# smart_hub_v2_1.net
KiCad netlist of a schematic drawn in EAGLE
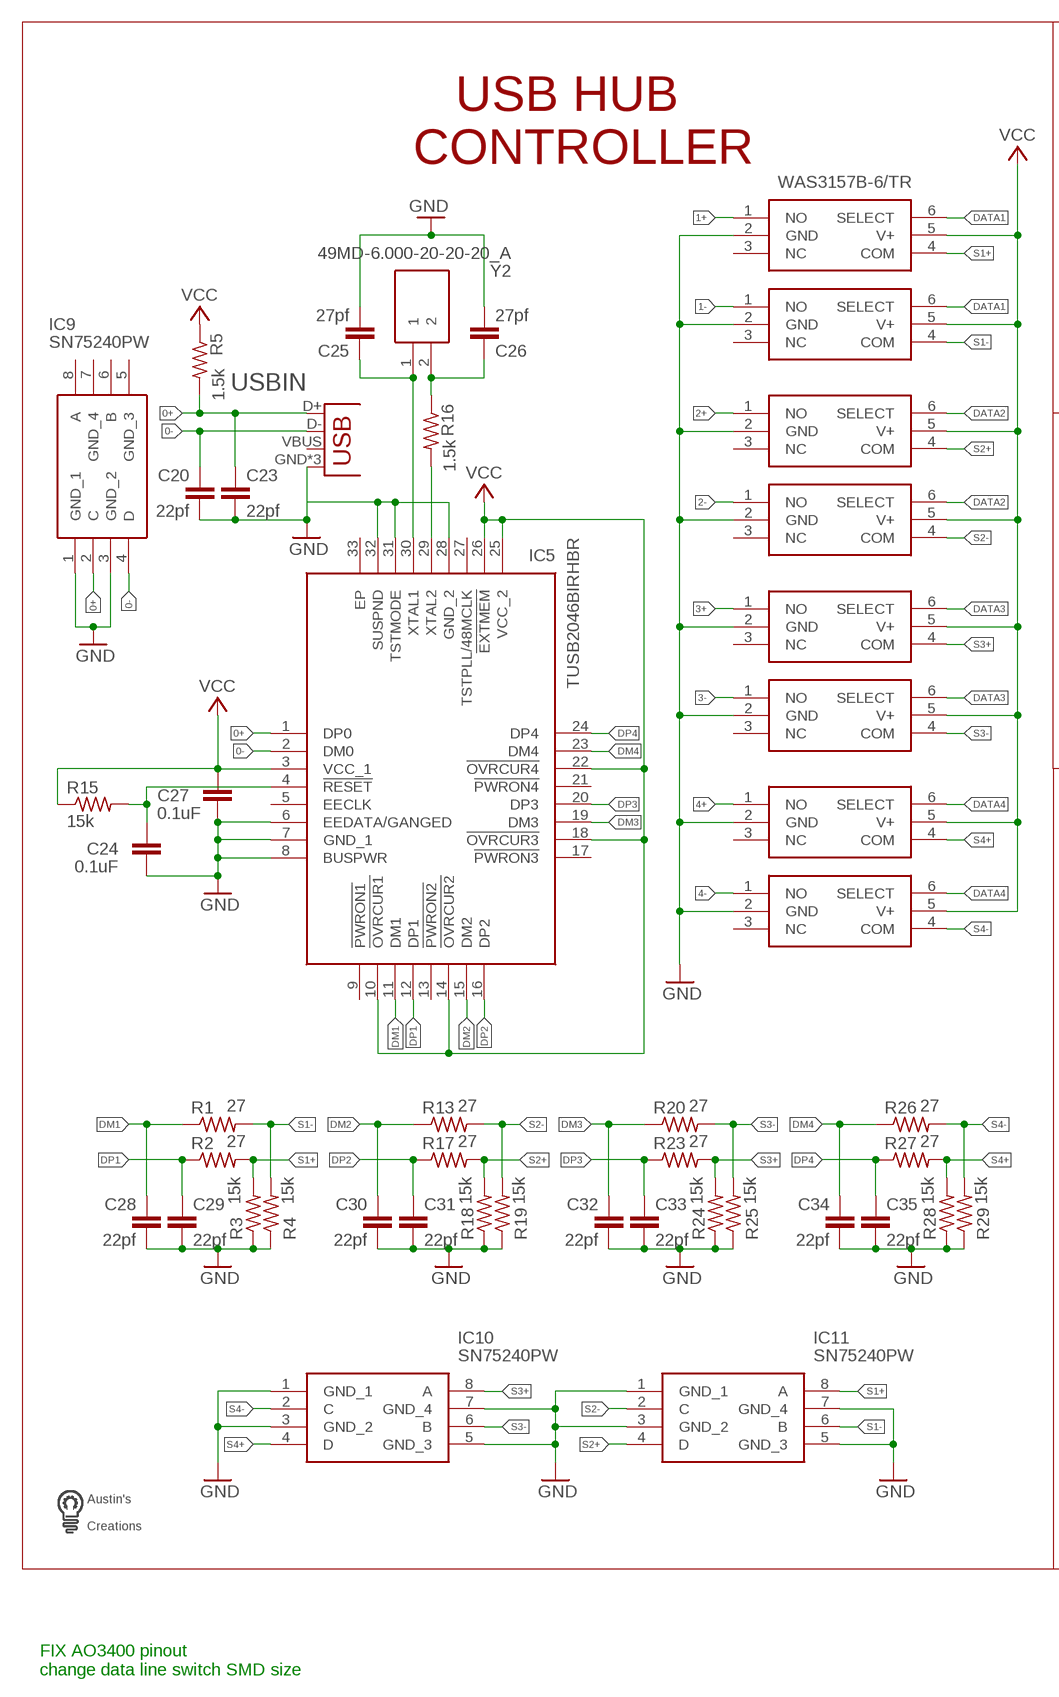
[diagram p0: schematic, sheet 1, part 1 of 2]
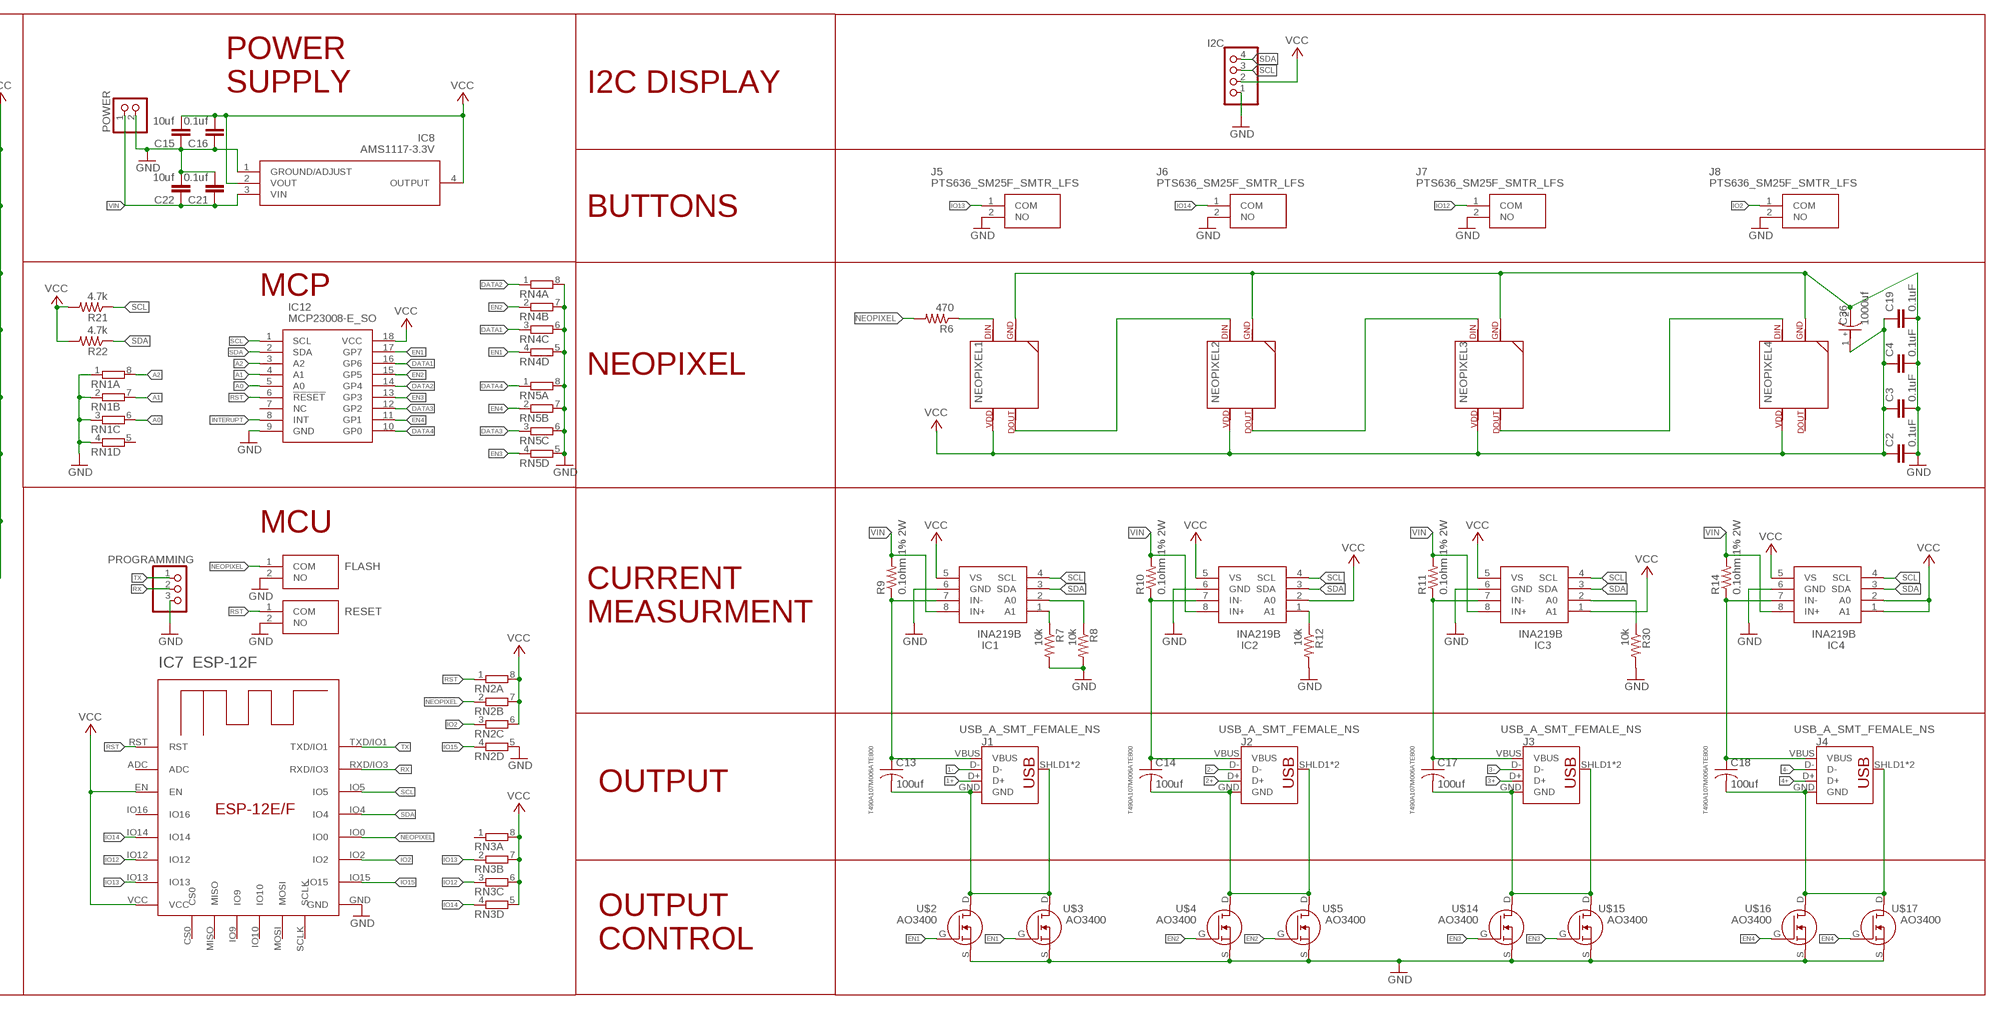
[diagram p1: schematic, sheet 1, part 2 of 2]

(export (version "E")
  (design (tool "Eeschema 10.0.6"))
  (components
    (comp (ref "C2")
      (value "0.1uF")
      (footprint "eagle-import:C0603")
      (libsource (lib "eagle-import") (part "C-EUC0603"))
    )
    (comp (ref "C3")
      (value "0.1uF")
      (footprint "eagle-import:C0603")
      (libsource (lib "eagle-import") (part "C-EUC0603"))
    )
    (comp (ref "C4")
      (value "0.1uF")
      (footprint "eagle-import:C0603")
      (libsource (lib "eagle-import") (part "C-EUC0603"))
    )
    (comp (ref "C13")
      (value "100uf")
      (footprint "eagle-import:C1206")
      (libsource (lib "eagle-import") (part "C-USC1206"))
    )
    (comp (ref "C14")
      (value "100uf")
      (footprint "eagle-import:C1206")
      (libsource (lib "eagle-import") (part "C-USC1206"))
    )
    (comp (ref "C15")
      (value "10uf")
      (footprint "eagle-import:C0603")
      (libsource (lib "eagle-import") (part "C-EUC0603"))
    )
    (comp (ref "C16")
      (value "0.1uf")
      (footprint "eagle-import:C0603")
      (libsource (lib "eagle-import") (part "C-EUC0603"))
    )
    (comp (ref "C17")
      (value "100uf")
      (footprint "eagle-import:C1206")
      (libsource (lib "eagle-import") (part "C-USC1206"))
    )
    (comp (ref "C18")
      (value "100uf")
      (footprint "eagle-import:C1206")
      (libsource (lib "eagle-import") (part "C-USC1206"))
    )
    (comp (ref "C19")
      (value "0.1uF")
      (footprint "eagle-import:C0603")
      (libsource (lib "eagle-import") (part "C-EUC0603"))
    )
    (comp (ref "C20")
      (value "22pf")
      (footprint "eagle-import:C0603")
      (libsource (lib "eagle-import") (part "C-EUC0603"))
    )
    (comp (ref "C21")
      (value "0.1uf")
      (footprint "eagle-import:C0603")
      (libsource (lib "eagle-import") (part "C-EUC0603"))
    )
    (comp (ref "C22")
      (value "10uf")
      (footprint "eagle-import:C0603")
      (libsource (lib "eagle-import") (part "C-EUC0603"))
    )
    (comp (ref "C23")
      (value "22pf")
      (footprint "eagle-import:C0603")
      (libsource (lib "eagle-import") (part "C-EUC0603"))
    )
    (comp (ref "C24")
      (value "0.1uF")
      (footprint "eagle-import:C0603")
      (libsource (lib "eagle-import") (part "C-EUC0603"))
    )
    (comp (ref "C25")
      (value "27pf")
      (footprint "eagle-import:C0603")
      (libsource (lib "eagle-import") (part "C-EUC0603"))
    )
    (comp (ref "C26")
      (value "27pf")
      (footprint "eagle-import:C0603")
      (libsource (lib "eagle-import") (part "C-EUC0603"))
    )
    (comp (ref "C27")
      (value "0.1uF")
      (footprint "eagle-import:C0603")
      (libsource (lib "eagle-import") (part "C-EUC0603"))
    )
    (comp (ref "C28")
      (value "22pf")
      (footprint "eagle-import:C0603")
      (libsource (lib "eagle-import") (part "C-EUC0603"))
    )
    (comp (ref "C29")
      (value "22pf")
      (footprint "eagle-import:C0603")
      (libsource (lib "eagle-import") (part "C-EUC0603"))
    )
    (comp (ref "C30")
      (value "22pf")
      (footprint "eagle-import:C0603")
      (libsource (lib "eagle-import") (part "C-EUC0603"))
    )
    (comp (ref "C31")
      (value "22pf")
      (footprint "eagle-import:C0603")
      (libsource (lib "eagle-import") (part "C-EUC0603"))
    )
    (comp (ref "C32")
      (value "22pf")
      (footprint "eagle-import:C0603")
      (libsource (lib "eagle-import") (part "C-EUC0603"))
    )
    (comp (ref "C33")
      (value "22pf")
      (footprint "eagle-import:C0603")
      (libsource (lib "eagle-import") (part "C-EUC0603"))
    )
    (comp (ref "C34")
      (value "22pf")
      (footprint "eagle-import:C0603")
      (libsource (lib "eagle-import") (part "C-EUC0603"))
    )
    (comp (ref "C35")
      (value "22pf")
      (footprint "eagle-import:C0603")
      (libsource (lib "eagle-import") (part "C-EUC0603"))
    )
    (comp (ref "C36")
      (value "1000uf")
      (footprint "eagle-import:CAPAE1030X1050N")
      (fields
        (field (name "MANUFACTURER_PART_NUMBER") "EEE-0JA102P")
        (field (name "MOUSER_PART_NUMBER") "667-EEE-0JA102P")
      )
      (libsource (lib "eagle-import") (part "EEE-0JA102P"))
    )
    (comp (ref "FLASH")
      (value "PTS636_SM25F_SMTR_LFS")
      (footprint "eagle-import:PTS636SM25FSMTRLFS")
      (fields
        (field (name "ARROW_PART_NUMBER") "PTS636 SM25F SMTR LFS")
        (field (name "MOUSER_PART_NUMBER") "611-PTS636SM25FSMTRL")
      )
      (libsource (lib "eagle-import") (part "PTS636_SM25F_SMTR_LFS"))
    )
    (comp (ref "I2C")
      (value "PINHD-1X4")
      (footprint "eagle-import:1X04")
      (libsource (lib "eagle-import") (part "PINHD-1X4"))
    )
    (comp (ref "IC1")
      (value "INA219B")
      (footprint "eagle-import:SOIC127P600X175-8N")
      (fields
        (field (name "ARROW_PART_NUMBER") "INA219AIDR")
        (field (name "MOUSER_PART_NUMBER") "595-INA219AIDR")
      )
      (libsource (lib "eagle-import") (part "INA219AIDR"))
    )
    (comp (ref "IC2")
      (value "INA219B")
      (footprint "eagle-import:SOIC127P600X175-8N")
      (fields
        (field (name "ARROW_PART_NUMBER") "INA219AIDR")
        (field (name "MOUSER_PART_NUMBER") "595-INA219AIDR")
      )
      (libsource (lib "eagle-import") (part "INA219AIDR"))
    )
    (comp (ref "IC3")
      (value "INA219B")
      (footprint "eagle-import:SOIC127P600X175-8N")
      (fields
        (field (name "ARROW_PART_NUMBER") "INA219AIDR")
        (field (name "MOUSER_PART_NUMBER") "595-INA219AIDR")
      )
      (libsource (lib "eagle-import") (part "INA219AIDR"))
    )
    (comp (ref "IC4")
      (value "INA219B")
      (footprint "eagle-import:SOIC127P600X175-8N")
      (fields
        (field (name "ARROW_PART_NUMBER") "INA219AIDR")
        (field (name "MOUSER_PART_NUMBER") "595-INA219AIDR")
      )
      (libsource (lib "eagle-import") (part "INA219AIDR"))
    )
    (comp (ref "IC5")
      (value "TUSB2046BIRHBR")
      (footprint "eagle-import:QFN50P500X500X100-33N")
      (fields (field (name "MOUSER_PART_NUMBER") "595-TUSB2046BIRHBR"))
      (libsource (lib "eagle-import") (part "TUSB2046BIRHBR"))
    )
    (comp (ref "IC7")
      (value "ESP-12F")
      (footprint "eagle-import:ESP-12E")
      (libsource (lib "eagle-import") (part "ESP-12E/F"))
    )
    (comp (ref "IC8")
      (value "AMS1117-3.3V")
      (footprint "eagle-import:SOT229P700X180-4N")
      (fields (field (name "MANUFACTURER_PART_NUMBER") "ams1117-3.3v"))
      (libsource (lib "eagle-import") (part "AMS1117-3.3V"))
    )
    (comp (ref "IC9")
      (value "SN75240PW")
      (footprint "eagle-import:SOP65P640X120-8N")
      (fields (field (name "MOUSER_PART_NUMBER") "595-SN75240PW"))
      (libsource (lib "eagle-import") (part "SN75240PW"))
    )
    (comp (ref "IC10")
      (value "SN75240PW")
      (footprint "eagle-import:SOP65P640X120-8N")
      (fields (field (name "MOUSER_PART_NUMBER") "595-SN75240PW"))
      (libsource (lib "eagle-import") (part "SN75240PW"))
    )
    (comp (ref "IC11")
      (value "SN75240PW")
      (footprint "eagle-import:SOP65P640X120-8N")
      (fields (field (name "MOUSER_PART_NUMBER") "595-SN75240PW"))
      (libsource (lib "eagle-import") (part "SN75240PW"))
    )
    (comp (ref "IC12")
      (value "MCP23008-E_SO")
      (footprint "eagle-import:SOIC127P1030X265-18N")
      (fields
        (field (name "ARROW_PART_NUMBER") "MCP23008-E/SO")
        (field (name "MOUSER_PART_NUMBER") "579-MCP23008-E/SO")
      )
      (libsource (lib "eagle-import") (part "MCP23008-E_SO"))
    )
    (comp (ref "J1")
      (value "USB_A_SMT_FEMALE_NS")
      (footprint "eagle-import:USB-A-S-NOSILK-FEMALE")
      (libsource (lib "eagle-import") (part "USB_A_SMT_FEMALE_NS"))
    )
    (comp (ref "J2")
      (value "USB_A_SMT_FEMALE_NS")
      (footprint "eagle-import:USB-A-S-NOSILK-FEMALE")
      (libsource (lib "eagle-import") (part "USB_A_SMT_FEMALE_NS"))
    )
    (comp (ref "J3")
      (value "USB_A_SMT_FEMALE_NS")
      (footprint "eagle-import:USB-A-S-NOSILK-FEMALE")
      (libsource (lib "eagle-import") (part "USB_A_SMT_FEMALE_NS"))
    )
    (comp (ref "J4")
      (value "USB_A_SMT_FEMALE_NS")
      (footprint "eagle-import:USB-A-S-NOSILK-FEMALE")
      (libsource (lib "eagle-import") (part "USB_A_SMT_FEMALE_NS"))
    )
    (comp (ref "J5")
      (value "PTS636_SM25F_SMTR_LFS")
      (footprint "eagle-import:PTS636SM25FSMTRLFS")
      (fields
        (field (name "ARROW_PART_NUMBER") "PTS636 SM25F SMTR LFS")
        (field (name "MOUSER_PART_NUMBER") "611-PTS636SM25FSMTRL")
      )
      (libsource (lib "eagle-import") (part "PTS636_SM25F_SMTR_LFS"))
    )
    (comp (ref "J6")
      (value "PTS636_SM25F_SMTR_LFS")
      (footprint "eagle-import:PTS636SM25FSMTRLFS")
      (fields
        (field (name "ARROW_PART_NUMBER") "PTS636 SM25F SMTR LFS")
        (field (name "MOUSER_PART_NUMBER") "611-PTS636SM25FSMTRL")
      )
      (libsource (lib "eagle-import") (part "PTS636_SM25F_SMTR_LFS"))
    )
    (comp (ref "J7")
      (value "PTS636_SM25F_SMTR_LFS")
      (footprint "eagle-import:PTS636SM25FSMTRLFS")
      (fields
        (field (name "ARROW_PART_NUMBER") "PTS636 SM25F SMTR LFS")
        (field (name "MOUSER_PART_NUMBER") "611-PTS636SM25FSMTRL")
      )
      (libsource (lib "eagle-import") (part "PTS636_SM25F_SMTR_LFS"))
    )
    (comp (ref "J8")
      (value "PTS636_SM25F_SMTR_LFS")
      (footprint "eagle-import:PTS636SM25FSMTRLFS")
      (fields
        (field (name "ARROW_PART_NUMBER") "PTS636 SM25F SMTR LFS")
        (field (name "MOUSER_PART_NUMBER") "611-PTS636SM25FSMTRL")
      )
      (libsource (lib "eagle-import") (part "PTS636_SM25F_SMTR_LFS"))
    )
    (comp (ref "NEOPIXEL1")
      (value "SK6812NEOPIXEL5050")
      (footprint "eagle-import:SK6812")
      (libsource (lib "eagle-import") (part "SK68125050NEOPIXEL"))
    )
    (comp (ref "NEOPIXEL2")
      (value "SK6812NEOPIXEL5050")
      (footprint "eagle-import:SK6812")
      (libsource (lib "eagle-import") (part "SK68125050NEOPIXEL"))
    )
    (comp (ref "NEOPIXEL3")
      (value "SK6812NEOPIXEL5050")
      (footprint "eagle-import:SK6812")
      (libsource (lib "eagle-import") (part "SK68125050NEOPIXEL"))
    )
    (comp (ref "NEOPIXEL4")
      (value "SK6812NEOPIXEL5050")
      (footprint "eagle-import:SK6812")
      (libsource (lib "eagle-import") (part "SK68125050NEOPIXEL"))
    )
    (comp (ref "POWER")
      (value "PINHD-1X2")
      (footprint "eagle-import:1X02")
      (libsource (lib "eagle-import") (part "PINHD-1X2"))
    )
    (comp (ref "PROGRAMMING")
      (value "PINHD-1X3")
      (footprint "eagle-import:1X03")
      (libsource (lib "eagle-import") (part "PINHD-1X3"))
    )
    (comp (ref "R1")
      (value "27")
      (footprint "eagle-import:R0603")
      (libsource (lib "eagle-import") (part "R-US_R0603"))
    )
    (comp (ref "R2")
      (value "27")
      (footprint "eagle-import:R0603")
      (libsource (lib "eagle-import") (part "R-US_R0603"))
    )
    (comp (ref "R3")
      (value "15k")
      (footprint "eagle-import:R0603")
      (libsource (lib "eagle-import") (part "R-US_R0603"))
    )
    (comp (ref "R4")
      (value "15k")
      (footprint "eagle-import:R0603")
      (libsource (lib "eagle-import") (part "R-US_R0603"))
    )
    (comp (ref "R5")
      (value "1.5k")
      (footprint "eagle-import:R0603")
      (libsource (lib "eagle-import") (part "R-US_R0603"))
    )
    (comp (ref "R6")
      (value "470")
      (footprint "eagle-import:R0603")
      (libsource (lib "eagle-import") (part "R-US_R0603"))
    )
    (comp (ref "R7")
      (value "10k")
      (footprint "eagle-import:R0603")
      (libsource (lib "eagle-import") (part "R-US_R0603"))
    )
    (comp (ref "R8")
      (value "10k")
      (footprint "eagle-import:R0603")
      (libsource (lib "eagle-import") (part "R-US_R0603"))
    )
    (comp (ref "R9")
      (value "0.1ohm 1% 2W")
      (footprint "eagle-import:R2512W")
      (libsource (lib "eagle-import") (part "R-US_R2512W"))
    )
    (comp (ref "R10")
      (value "0.1ohm 1% 2W")
      (footprint "eagle-import:R2512W")
      (libsource (lib "eagle-import") (part "R-US_R2512W"))
    )
    (comp (ref "R11")
      (value "0.1ohm 1% 2W")
      (footprint "eagle-import:R2512W")
      (libsource (lib "eagle-import") (part "R-US_R2512W"))
    )
    (comp (ref "R12")
      (value "10k")
      (footprint "eagle-import:R0603")
      (libsource (lib "eagle-import") (part "R-US_R0603"))
    )
    (comp (ref "R13")
      (value "27")
      (footprint "eagle-import:R0603")
      (libsource (lib "eagle-import") (part "R-US_R0603"))
    )
    (comp (ref "R14")
      (value "0.1ohm 1% 2W")
      (footprint "eagle-import:R2512W")
      (libsource (lib "eagle-import") (part "R-US_R2512W"))
    )
    (comp (ref "R15")
      (value "15k")
      (footprint "eagle-import:R0603")
      (libsource (lib "eagle-import") (part "R-US_R0603"))
    )
    (comp (ref "R16")
      (value "1.5k")
      (footprint "eagle-import:R0603")
      (libsource (lib "eagle-import") (part "R-US_R0603"))
    )
    (comp (ref "R17")
      (value "27")
      (footprint "eagle-import:R0603")
      (libsource (lib "eagle-import") (part "R-US_R0603"))
    )
    (comp (ref "R18")
      (value "15k")
      (footprint "eagle-import:R0603")
      (libsource (lib "eagle-import") (part "R-US_R0603"))
    )
    (comp (ref "R19")
      (value "15k")
      (footprint "eagle-import:R0603")
      (libsource (lib "eagle-import") (part "R-US_R0603"))
    )
    (comp (ref "R20")
      (value "27")
      (footprint "eagle-import:R0603")
      (libsource (lib "eagle-import") (part "R-US_R0603"))
    )
    (comp (ref "R21")
      (value "4.7k")
      (footprint "eagle-import:R0603")
      (libsource (lib "eagle-import") (part "R-US_R0603"))
    )
    (comp (ref "R22")
      (value "4.7k")
      (footprint "eagle-import:R0603")
      (libsource (lib "eagle-import") (part "R-US_R0603"))
    )
    (comp (ref "R23")
      (value "27")
      (footprint "eagle-import:R0603")
      (libsource (lib "eagle-import") (part "R-US_R0603"))
    )
    (comp (ref "R24")
      (value "15k")
      (footprint "eagle-import:R0603")
      (libsource (lib "eagle-import") (part "R-US_R0603"))
    )
    (comp (ref "R25")
      (value "15k")
      (footprint "eagle-import:R0603")
      (libsource (lib "eagle-import") (part "R-US_R0603"))
    )
    (comp (ref "R26")
      (value "27")
      (footprint "eagle-import:R0603")
      (libsource (lib "eagle-import") (part "R-US_R0603"))
    )
    (comp (ref "R27")
      (value "27")
      (footprint "eagle-import:R0603")
      (libsource (lib "eagle-import") (part "R-US_R0603"))
    )
    (comp (ref "R28")
      (value "15k")
      (footprint "eagle-import:R0603")
      (libsource (lib "eagle-import") (part "R-US_R0603"))
    )
    (comp (ref "R29")
      (value "15k")
      (footprint "eagle-import:R0603")
      (libsource (lib "eagle-import") (part "R-US_R0603"))
    )
    (comp (ref "R30")
      (value "10k")
      (footprint "eagle-import:R0603")
      (libsource (lib "eagle-import") (part "R-US_R0603"))
    )
    (comp (ref "RESET")
      (value "PTS636_SM25F_SMTR_LFS")
      (footprint "eagle-import:PTS636SM25FSMTRLFS")
      (fields
        (field (name "ARROW_PART_NUMBER") "PTS636 SM25F SMTR LFS")
        (field (name "MOUSER_PART_NUMBER") "611-PTS636SM25FSMTRL")
      )
      (libsource (lib "eagle-import") (part "PTS636_SM25F_SMTR_LFS"))
    )
    (comp (ref "RN1")
      (value "4R-N0603-ARC")
      (footprint "eagle-import:0603-ARC")
      (libsource (lib "eagle-import") (part "4R-N0603-ARC"))
    )
    (comp (ref "RN2")
      (value "4R-N0603-ARC")
      (footprint "eagle-import:0603-ARC")
      (libsource (lib "eagle-import") (part "4R-N0603-ARC"))
    )
    (comp (ref "RN3")
      (value "4R-N0603-ARC")
      (footprint "eagle-import:0603-ARC")
      (libsource (lib "eagle-import") (part "4R-N0603-ARC"))
    )
    (comp (ref "RN4")
      (value "4R-N0603-ARC")
      (footprint "eagle-import:0603-ARC")
      (libsource (lib "eagle-import") (part "4R-N0603-ARC"))
    )
    (comp (ref "RN5")
      (value "4R-N0603-ARC")
      (footprint "eagle-import:0603-ARC")
      (libsource (lib "eagle-import") (part "4R-N0603-ARC"))
    )
    (comp (ref "U$1")
      (value "LOGOMASSIVE")
      (footprint "eagle-import:LOGOMASSIVE")
      (libsource (lib "eagle-import") (part "LOGOMASSIVE"))
    )
    (comp (ref "U$2")
      (value "AO3400")
      (footprint "eagle-import:AO3400")
      (libsource (lib "eagle-import") (part "AO3400"))
    )
    (comp (ref "U$3")
      (value "AO3400")
      (footprint "eagle-import:AO3400")
      (libsource (lib "eagle-import") (part "AO3400"))
    )
    (comp (ref "U$4")
      (value "AO3400")
      (footprint "eagle-import:AO3400")
      (libsource (lib "eagle-import") (part "AO3400"))
    )
    (comp (ref "U$5")
      (value "AO3400")
      (footprint "eagle-import:AO3400")
      (libsource (lib "eagle-import") (part "AO3400"))
    )
    (comp (ref "U$6")
      (value "WAS3157B-6/TR")
      (footprint "eagle-import:WAS3157B-6_TR")
      (libsource (lib "eagle-import") (part "WAS3157B-6/TR"))
    )
    (comp (ref "U$7")
      (value "WAS3157B-6/TR")
      (footprint "eagle-import:WAS3157B-6_TR")
      (libsource (lib "eagle-import") (part "WAS3157B-6/TR"))
    )
    (comp (ref "U$8")
      (value "WAS3157B-6/TR")
      (footprint "eagle-import:WAS3157B-6_TR")
      (libsource (lib "eagle-import") (part "WAS3157B-6/TR"))
    )
    (comp (ref "U$9")
      (value "WAS3157B-6/TR")
      (footprint "eagle-import:WAS3157B-6_TR")
      (libsource (lib "eagle-import") (part "WAS3157B-6/TR"))
    )
    (comp (ref "U$10")
      (value "WAS3157B-6/TR")
      (footprint "eagle-import:WAS3157B-6_TR")
      (libsource (lib "eagle-import") (part "WAS3157B-6/TR"))
    )
    (comp (ref "U$11")
      (value "WAS3157B-6/TR")
      (footprint "eagle-import:WAS3157B-6_TR")
      (libsource (lib "eagle-import") (part "WAS3157B-6/TR"))
    )
    (comp (ref "U$12")
      (value "WAS3157B-6/TR")
      (footprint "eagle-import:WAS3157B-6_TR")
      (libsource (lib "eagle-import") (part "WAS3157B-6/TR"))
    )
    (comp (ref "U$13")
      (value "WAS3157B-6/TR")
      (footprint "eagle-import:WAS3157B-6_TR")
      (libsource (lib "eagle-import") (part "WAS3157B-6/TR"))
    )
    (comp (ref "U$14")
      (value "AO3400")
      (footprint "eagle-import:AO3400")
      (libsource (lib "eagle-import") (part "AO3400"))
    )
    (comp (ref "U$15")
      (value "AO3400")
      (footprint "eagle-import:AO3400")
      (libsource (lib "eagle-import") (part "AO3400"))
    )
    (comp (ref "U$16")
      (value "AO3400")
      (footprint "eagle-import:AO3400")
      (libsource (lib "eagle-import") (part "AO3400"))
    )
    (comp (ref "U$17")
      (value "AO3400")
      (footprint "eagle-import:AO3400")
      (libsource (lib "eagle-import") (part "AO3400"))
    )
    (comp (ref "USBIN")
      (value "USB-MICROB")
      (footprint "eagle-import:USB-MICROB")
      (libsource (lib "eagle-import") (part "USB-MICROB"))
    )
    (comp (ref "Y2")
      (value "49MD-6.000-20-20-20_A")
      (footprint "eagle-import:49MD6000202020A")
      (fields (field (name "MANUFACTURER_PART_NUMBER") "49MD-6.000-20-20-20/A"))
      (libsource (lib "eagle-import") (part "49MD-6.000-20-20-20_A"))
    )
  )
  (nets
    (net (code "1") (name "0+") (class "Default")
      (node (ref "C23") (pin "1") (pinfunction "1_1") (pintype "passive"))
      (node (ref "IC5") (pin "1") (pinfunction "DP0_1") (pintype "bidirectional"))
      (node (ref "IC9") (pin "2") (pinfunction "C_2") (pintype "bidirectional"))
      (node (ref "R5") (pin "2") (pinfunction "2_2") (pintype "passive"))
      (node (ref "USBIN") (pin "D+") (pinfunction "D+_D+") (pintype "bidirectional"))
    )
    (net (code "2") (name "0-") (class "Default")
      (node (ref "C20") (pin "1") (pinfunction "1_1") (pintype "passive"))
      (node (ref "IC5") (pin "2") (pinfunction "DM0_2") (pintype "bidirectional"))
      (node (ref "IC9") (pin "4") (pinfunction "D_4") (pintype "bidirectional"))
      (node (ref "USBIN") (pin "D-") (pinfunction "D-_D-") (pintype "bidirectional"))
    )
    (net (code "3") (name "1+") (class "Default")
      (node (ref "J1") (pin "D+") (pinfunction "D+_D+") (pintype "bidirectional"))
      (node (ref "U$6") (pin "1") (pinfunction "NO_1") (pintype "bidirectional"))
    )
    (net (code "4") (name "1-") (class "Default")
      (node (ref "J1") (pin "D-") (pinfunction "D-_D-") (pintype "bidirectional"))
      (node (ref "U$7") (pin "1") (pinfunction "NO_1") (pintype "bidirectional"))
    )
    (net (code "5") (name "2+") (class "Default")
      (node (ref "J2") (pin "D+") (pinfunction "D+_D+") (pintype "bidirectional"))
      (node (ref "U$8") (pin "1") (pinfunction "NO_1") (pintype "bidirectional"))
    )
    (net (code "6") (name "2-") (class "Default")
      (node (ref "J2") (pin "D-") (pinfunction "D-_D-") (pintype "bidirectional"))
      (node (ref "U$9") (pin "1") (pinfunction "NO_1") (pintype "bidirectional"))
    )
    (net (code "7") (name "3+") (class "Default")
      (node (ref "J3") (pin "D+") (pinfunction "D+_D+") (pintype "bidirectional"))
      (node (ref "U$10") (pin "1") (pinfunction "NO_1") (pintype "bidirectional"))
    )
    (net (code "8") (name "3-") (class "Default")
      (node (ref "J3") (pin "D-") (pinfunction "D-_D-") (pintype "bidirectional"))
      (node (ref "U$11") (pin "1") (pinfunction "NO_1") (pintype "bidirectional"))
    )
    (net (code "9") (name "4+") (class "Default")
      (node (ref "J4") (pin "D+") (pinfunction "D+_D+") (pintype "bidirectional"))
      (node (ref "U$12") (pin "1") (pinfunction "NO_1") (pintype "bidirectional"))
    )
    (net (code "10") (name "4-") (class "Default")
      (node (ref "J4") (pin "D-") (pinfunction "D-_D-") (pintype "bidirectional"))
      (node (ref "U$13") (pin "1") (pinfunction "NO_1") (pintype "bidirectional"))
    )
    (net (code "11") (name "A0") (class "Default")
      (node (ref "IC12") (pin "5") (pinfunction "A0_5") (pintype "bidirectional"))
      (node (ref "RN1") (pin "6") (pinfunction "2_6") (pintype "passive"))
    )
    (net (code "12") (name "A1") (class "Default")
      (node (ref "IC12") (pin "4") (pinfunction "A1_4") (pintype "bidirectional"))
      (node (ref "RN1") (pin "7") (pinfunction "2_7") (pintype "passive"))
    )
    (net (code "13") (name "A2") (class "Default")
      (node (ref "IC12") (pin "3") (pinfunction "A2_3") (pintype "bidirectional"))
      (node (ref "RN1") (pin "8") (pinfunction "2_8") (pintype "passive"))
    )
    (net (code "14") (name "DATA1") (class "Default")
      (node (ref "IC12") (pin "16") (pinfunction "GP6_16") (pintype "bidirectional"))
      (node (ref "RN4") (pin "3") (pinfunction "1_3") (pintype "passive"))
      (node (ref "U$6") (pin "6") (pinfunction "SELECT_6") (pintype "bidirectional"))
      (node (ref "U$7") (pin "6") (pinfunction "SELECT_6") (pintype "bidirectional"))
    )
    (net (code "15") (name "DATA2") (class "Default")
      (node (ref "IC12") (pin "14") (pinfunction "GP4_14") (pintype "bidirectional"))
      (node (ref "RN4") (pin "1") (pinfunction "1_1") (pintype "passive"))
      (node (ref "U$8") (pin "6") (pinfunction "SELECT_6") (pintype "bidirectional"))
      (node (ref "U$9") (pin "6") (pinfunction "SELECT_6") (pintype "bidirectional"))
    )
    (net (code "16") (name "DATA3") (class "Default")
      (node (ref "IC12") (pin "12") (pinfunction "GP2_12") (pintype "bidirectional"))
      (node (ref "RN5") (pin "3") (pinfunction "1_3") (pintype "passive"))
      (node (ref "U$10") (pin "6") (pinfunction "SELECT_6") (pintype "bidirectional"))
      (node (ref "U$11") (pin "6") (pinfunction "SELECT_6") (pintype "bidirectional"))
    )
    (net (code "17") (name "DATA4") (class "Default")
      (node (ref "IC12") (pin "10") (pinfunction "GP0_10") (pintype "bidirectional"))
      (node (ref "RN5") (pin "1") (pinfunction "1_1") (pintype "passive"))
      (node (ref "U$12") (pin "6") (pinfunction "SELECT_6") (pintype "bidirectional"))
      (node (ref "U$13") (pin "6") (pinfunction "SELECT_6") (pintype "bidirectional"))
    )
    (net (code "18") (name "DM1") (class "Default")
      (node (ref "C28") (pin "1") (pinfunction "1_1") (pintype "passive"))
      (node (ref "IC5") (pin "11") (pinfunction "DM1_11") (pintype "bidirectional"))
      (node (ref "R1") (pin "1") (pinfunction "1_1") (pintype "passive"))
    )
    (net (code "19") (name "DM2") (class "Default")
      (node (ref "C30") (pin "1") (pinfunction "1_1") (pintype "passive"))
      (node (ref "IC5") (pin "15") (pinfunction "DM2_15") (pintype "bidirectional"))
      (node (ref "R13") (pin "1") (pinfunction "1_1") (pintype "passive"))
    )
    (net (code "20") (name "DM3") (class "Default")
      (node (ref "C32") (pin "1") (pinfunction "1_1") (pintype "passive"))
      (node (ref "IC5") (pin "19") (pinfunction "DM3_19") (pintype "bidirectional"))
      (node (ref "R20") (pin "1") (pinfunction "1_1") (pintype "passive"))
    )
    (net (code "21") (name "DM4") (class "Default")
      (node (ref "C34") (pin "1") (pinfunction "1_1") (pintype "passive"))
      (node (ref "IC5") (pin "23") (pinfunction "DM4_23") (pintype "bidirectional"))
      (node (ref "R26") (pin "1") (pinfunction "1_1") (pintype "passive"))
    )
    (net (code "22") (name "DP1") (class "Default")
      (node (ref "C29") (pin "1") (pinfunction "1_1") (pintype "passive"))
      (node (ref "IC5") (pin "12") (pinfunction "DP1_12") (pintype "bidirectional"))
      (node (ref "R2") (pin "1") (pinfunction "1_1") (pintype "passive"))
    )
    (net (code "23") (name "DP2") (class "Default")
      (node (ref "C31") (pin "1") (pinfunction "1_1") (pintype "passive"))
      (node (ref "IC5") (pin "16") (pinfunction "DP2_16") (pintype "bidirectional"))
      (node (ref "R17") (pin "1") (pinfunction "1_1") (pintype "passive"))
    )
    (net (code "24") (name "DP3") (class "Default")
      (node (ref "C33") (pin "1") (pinfunction "1_1") (pintype "passive"))
      (node (ref "IC5") (pin "20") (pinfunction "DP3_20") (pintype "bidirectional"))
      (node (ref "R23") (pin "1") (pinfunction "1_1") (pintype "passive"))
    )
    (net (code "25") (name "DP4") (class "Default")
      (node (ref "C35") (pin "1") (pinfunction "1_1") (pintype "passive"))
      (node (ref "IC5") (pin "24") (pinfunction "DP4_24") (pintype "bidirectional"))
      (node (ref "R27") (pin "1") (pinfunction "1_1") (pintype "passive"))
    )
    (net (code "26") (name "EN1") (class "Default")
      (node (ref "IC12") (pin "17") (pinfunction "GP7_17") (pintype "bidirectional"))
      (node (ref "RN4") (pin "4") (pinfunction "1_4") (pintype "passive"))
      (node (ref "U$2") (pin "G") (pinfunction "G_G") (pintype "bidirectional"))
      (node (ref "U$3") (pin "G") (pinfunction "G_G") (pintype "bidirectional"))
    )
    (net (code "27") (name "EN2") (class "Default")
      (node (ref "IC12") (pin "15") (pinfunction "GP5_15") (pintype "bidirectional"))
      (node (ref "RN4") (pin "2") (pinfunction "1_2") (pintype "passive"))
      (node (ref "U$4") (pin "G") (pinfunction "G_G") (pintype "bidirectional"))
      (node (ref "U$5") (pin "G") (pinfunction "G_G") (pintype "bidirectional"))
    )
    (net (code "28") (name "EN3") (class "Default")
      (node (ref "IC12") (pin "13") (pinfunction "GP3_13") (pintype "bidirectional"))
      (node (ref "RN5") (pin "4") (pinfunction "1_4") (pintype "passive"))
      (node (ref "U$14") (pin "G") (pinfunction "G_G") (pintype "bidirectional"))
      (node (ref "U$15") (pin "G") (pinfunction "G_G") (pintype "bidirectional"))
    )
    (net (code "29") (name "EN4") (class "Default")
      (node (ref "IC12") (pin "11") (pinfunction "GP1_11") (pintype "bidirectional"))
      (node (ref "RN5") (pin "2") (pinfunction "1_2") (pintype "passive"))
      (node (ref "U$16") (pin "G") (pinfunction "G_G") (pintype "bidirectional"))
      (node (ref "U$17") (pin "G") (pinfunction "G_G") (pintype "bidirectional"))
    )
    (net (code "30") (name "GND") (class "Default")
      (node (ref "C15") (pin "1") (pinfunction "1_1") (pintype "passive"))
      (node (ref "C16") (pin "1") (pinfunction "1_1") (pintype "passive"))
      (node (ref "C19") (pin "2") (pinfunction "2_2") (pintype "passive"))
      (node (ref "C2") (pin "2") (pinfunction "2_2") (pintype "passive"))
      (node (ref "C20") (pin "2") (pinfunction "2_2") (pintype "passive"))
      (node (ref "C21") (pin "2") (pinfunction "2_2") (pintype "passive"))
      (node (ref "C22") (pin "2") (pinfunction "2_2") (pintype "passive"))
      (node (ref "C23") (pin "2") (pinfunction "2_2") (pintype "passive"))
      (node (ref "C24") (pin "2") (pinfunction "2_2") (pintype "passive"))
      (node (ref "C25") (pin "2") (pinfunction "2_2") (pintype "passive"))
      (node (ref "C26") (pin "2") (pinfunction "2_2") (pintype "passive"))
      (node (ref "C27") (pin "2") (pinfunction "2_2") (pintype "passive"))
      (node (ref "C28") (pin "2") (pinfunction "2_2") (pintype "passive"))
      (node (ref "C29") (pin "2") (pinfunction "2_2") (pintype "passive"))
      (node (ref "C3") (pin "2") (pinfunction "2_2") (pintype "passive"))
      (node (ref "C30") (pin "2") (pinfunction "2_2") (pintype "passive"))
      (node (ref "C31") (pin "2") (pinfunction "2_2") (pintype "passive"))
      (node (ref "C32") (pin "2") (pinfunction "2_2") (pintype "passive"))
      (node (ref "C33") (pin "2") (pinfunction "2_2") (pintype "passive"))
      (node (ref "C34") (pin "2") (pinfunction "2_2") (pintype "passive"))
      (node (ref "C35") (pin "2") (pinfunction "2_2") (pintype "passive"))
      (node (ref "C36") (pin "2") (pinfunction "-_2") (pintype "bidirectional"))
      (node (ref "C4") (pin "2") (pinfunction "2_2") (pintype "passive"))
      (node (ref "FLASH") (pin "2") (pinfunction "NO_2") (pintype "bidirectional"))
      (node (ref "I2C") (pin "1") (pinfunction "1_1") (pintype "passive"))
      (node (ref "IC1") (pin "6") (pinfunction "GND_6") (pintype "bidirectional"))
      (node (ref "IC10") (pin "1") (pinfunction "GND_1_1") (pintype "bidirectional"))
      (node (ref "IC10") (pin "3") (pinfunction "GND_2_3") (pintype "bidirectional"))
      (node (ref "IC10") (pin "5") (pinfunction "GND_3_5") (pintype "bidirectional"))
      (node (ref "IC10") (pin "7") (pinfunction "GND_4_7") (pintype "bidirectional"))
      (node (ref "IC11") (pin "1") (pinfunction "GND_1_1") (pintype "bidirectional"))
      (node (ref "IC11") (pin "3") (pinfunction "GND_2_3") (pintype "bidirectional"))
      (node (ref "IC11") (pin "5") (pinfunction "GND_3_5") (pintype "bidirectional"))
      (node (ref "IC11") (pin "7") (pinfunction "GND_4_7") (pintype "bidirectional"))
      (node (ref "IC12") (pin "9") (pinfunction "GND_9") (pintype "bidirectional"))
      (node (ref "IC2") (pin "6") (pinfunction "GND_6") (pintype "bidirectional"))
      (node (ref "IC3") (pin "6") (pinfunction "GND_6") (pintype "bidirectional"))
      (node (ref "IC4") (pin "6") (pinfunction "GND_6") (pintype "bidirectional"))
      (node (ref "IC5") (pin "28") (pinfunction "GND_2_28") (pintype "bidirectional"))
      (node (ref "IC5") (pin "31") (pinfunction "TSTMODE_31") (pintype "bidirectional"))
      (node (ref "IC5") (pin "32") (pinfunction "SUSPND_32") (pintype "bidirectional"))
      (node (ref "IC5") (pin "6") (pinfunction "EEDATA/GANGED_6") (pintype "bidirectional"))
      (node (ref "IC5") (pin "7") (pinfunction "GND_1_7") (pintype "bidirectional"))
      (node (ref "IC5") (pin "8") (pinfunction "BUSPWR_8") (pintype "bidirectional"))
      (node (ref "IC7") (pin "GND") (pinfunction "GND_GND") (pintype "power_in"))
      (node (ref "IC8") (pin "1") (pinfunction "GROUND/ADJUST_1") (pintype "bidirectional"))
      (node (ref "IC9") (pin "1") (pinfunction "GND_1_1") (pintype "bidirectional"))
      (node (ref "IC9") (pin "3") (pinfunction "GND_2_3") (pintype "bidirectional"))
      (node (ref "J5") (pin "2") (pinfunction "NO_2") (pintype "bidirectional"))
      (node (ref "J6") (pin "2") (pinfunction "NO_2") (pintype "bidirectional"))
      (node (ref "J7") (pin "2") (pinfunction "NO_2") (pintype "bidirectional"))
      (node (ref "J8") (pin "2") (pinfunction "NO_2") (pintype "bidirectional"))
      (node (ref "NEOPIXEL1") (pin "3") (pinfunction "GND_3") (pintype "bidirectional"))
      (node (ref "NEOPIXEL2") (pin "3") (pinfunction "GND_3") (pintype "bidirectional"))
      (node (ref "NEOPIXEL3") (pin "3") (pinfunction "GND_3") (pintype "bidirectional"))
      (node (ref "NEOPIXEL4") (pin "3") (pinfunction "GND_3") (pintype "bidirectional"))
      (node (ref "POWER") (pin "2") (pinfunction "2_2") (pintype "passive"))
      (node (ref "PROGRAMMING") (pin "3") (pinfunction "3_3") (pintype "passive"))
      (node (ref "R12") (pin "2") (pinfunction "2_2") (pintype "passive"))
      (node (ref "R18") (pin "1") (pinfunction "1_1") (pintype "passive"))
      (node (ref "R19") (pin "1") (pinfunction "1_1") (pintype "passive"))
      (node (ref "R24") (pin "1") (pinfunction "1_1") (pintype "passive"))
      (node (ref "R25") (pin "1") (pinfunction "1_1") (pintype "passive"))
      (node (ref "R28") (pin "1") (pinfunction "1_1") (pintype "passive"))
      (node (ref "R29") (pin "1") (pinfunction "1_1") (pintype "passive"))
      (node (ref "R3") (pin "1") (pinfunction "1_1") (pintype "passive"))
      (node (ref "R30") (pin "2") (pinfunction "2_2") (pintype "passive"))
      (node (ref "R4") (pin "1") (pinfunction "1_1") (pintype "passive"))
      (node (ref "R7") (pin "2") (pinfunction "2_2") (pintype "passive"))
      (node (ref "R8") (pin "2") (pinfunction "2_2") (pintype "passive"))
      (node (ref "RESET") (pin "2") (pinfunction "NO_2") (pintype "bidirectional"))
      (node (ref "RN1") (pin "1") (pinfunction "1_1") (pintype "passive"))
      (node (ref "RN1") (pin "2") (pinfunction "1_2") (pintype "passive"))
      (node (ref "RN1") (pin "3") (pinfunction "1_3") (pintype "passive"))
      (node (ref "RN1") (pin "4") (pinfunction "1_4") (pintype "passive"))
      (node (ref "RN2") (pin "5") (pinfunction "2_5") (pintype "passive"))
      (node (ref "RN4") (pin "5") (pinfunction "2_5") (pintype "passive"))
      (node (ref "RN4") (pin "6") (pinfunction "2_6") (pintype "passive"))
      (node (ref "RN4") (pin "7") (pinfunction "2_7") (pintype "passive"))
      (node (ref "RN4") (pin "8") (pinfunction "2_8") (pintype "passive"))
      (node (ref "RN5") (pin "5") (pinfunction "2_5") (pintype "passive"))
      (node (ref "RN5") (pin "6") (pinfunction "2_6") (pintype "passive"))
      (node (ref "RN5") (pin "7") (pinfunction "2_7") (pintype "passive"))
      (node (ref "RN5") (pin "8") (pinfunction "2_8") (pintype "passive"))
      (node (ref "U$10") (pin "2") (pinfunction "GND_2") (pintype "bidirectional"))
      (node (ref "U$11") (pin "2") (pinfunction "GND_2") (pintype "bidirectional"))
      (node (ref "U$12") (pin "2") (pinfunction "GND_2") (pintype "bidirectional"))
      (node (ref "U$13") (pin "2") (pinfunction "GND_2") (pintype "bidirectional"))
      (node (ref "U$14") (pin "S") (pinfunction "S_S") (pintype "bidirectional"))
      (node (ref "U$15") (pin "S") (pinfunction "S_S") (pintype "bidirectional"))
      (node (ref "U$16") (pin "S") (pinfunction "S_S") (pintype "bidirectional"))
      (node (ref "U$17") (pin "S") (pinfunction "S_S") (pintype "bidirectional"))
      (node (ref "U$2") (pin "S") (pinfunction "S_S") (pintype "bidirectional"))
      (node (ref "U$3") (pin "S") (pinfunction "S_S") (pintype "bidirectional"))
      (node (ref "U$4") (pin "S") (pinfunction "S_S") (pintype "bidirectional"))
      (node (ref "U$5") (pin "S") (pinfunction "S_S") (pintype "bidirectional"))
      (node (ref "U$6") (pin "2") (pinfunction "GND_2") (pintype "bidirectional"))
      (node (ref "U$7") (pin "2") (pinfunction "GND_2") (pintype "bidirectional"))
      (node (ref "U$8") (pin "2") (pinfunction "GND_2") (pintype "bidirectional"))
      (node (ref "U$9") (pin "2") (pinfunction "GND_2") (pintype "bidirectional"))
      (node (ref "USBIN") (pin "GND") (pinfunction "GND_GND") (pintype "bidirectional"))
      (node (ref "USBIN") (pin "MT1") (pinfunction "GND_MT1") (pintype "bidirectional"))
      (node (ref "USBIN") (pin "MT2") (pinfunction "GND_MT2") (pintype "bidirectional"))
    )
    (net (code "31") (name "INTERUPT") (class "Default")
      (node (ref "IC12") (pin "8") (pinfunction "INT_8") (pintype "bidirectional"))
    )
    (net (code "32") (name "IO2") (class "Default")
      (node (ref "IC7") (pin "IO2") (pinfunction "IO2_IO2") (pintype "bidirectional"))
      (node (ref "J8") (pin "1") (pinfunction "COM_1") (pintype "bidirectional"))
      (node (ref "RN2") (pin "3") (pinfunction "1_3") (pintype "passive"))
    )
    (net (code "33") (name "IO12") (class "Default")
      (node (ref "IC7") (pin "IO12") (pinfunction "IO12_IO12") (pintype "bidirectional"))
      (node (ref "J7") (pin "1") (pinfunction "COM_1") (pintype "bidirectional"))
      (node (ref "RN3") (pin "3") (pinfunction "1_3") (pintype "passive"))
    )
    (net (code "34") (name "IO13") (class "Default")
      (node (ref "IC7") (pin "IO13") (pinfunction "IO13_IO13") (pintype "bidirectional"))
      (node (ref "J5") (pin "1") (pinfunction "COM_1") (pintype "bidirectional"))
      (node (ref "RN3") (pin "2") (pinfunction "1_2") (pintype "passive"))
    )
    (net (code "35") (name "IO14") (class "Default")
      (node (ref "IC7") (pin "IO14") (pinfunction "IO14_IO14") (pintype "bidirectional"))
      (node (ref "J6") (pin "1") (pinfunction "COM_1") (pintype "bidirectional"))
      (node (ref "RN3") (pin "4") (pinfunction "1_4") (pintype "passive"))
    )
    (net (code "36") (name "IO15") (class "Default")
      (node (ref "IC7") (pin "IO15") (pinfunction "IO15_IO15") (pintype "bidirectional"))
      (node (ref "RN2") (pin "4") (pinfunction "1_4") (pintype "passive"))
    )
    (net (code "37") (name "NEOPIXEL") (class "Default")
      (node (ref "FLASH") (pin "1") (pinfunction "COM_1") (pintype "bidirectional"))
      (node (ref "IC7") (pin "IO0") (pinfunction "IO0_IO0") (pintype "bidirectional"))
      (node (ref "R6") (pin "2") (pinfunction "2_2") (pintype "passive"))
      (node (ref "RN2") (pin "2") (pinfunction "1_2") (pintype "passive"))
    )
    (net (code "38") (name "Net-(C13-Pad2)") (class "Default")
      (node (ref "C13") (pin "2") (pinfunction "2_2") (pintype "passive"))
      (node (ref "J1") (pin "GND") (pinfunction "GND_GND") (pintype "power_in"))
      (node (ref "J1") (pin "SHLD1") (pinfunction "SHIELD_SHLD1") (pintype "bidirectional"))
      (node (ref "J1") (pin "SHLD2") (pinfunction "SHIELD_SHLD2") (pintype "bidirectional"))
      (node (ref "U$2") (pin "D") (pinfunction "D_D") (pintype "bidirectional"))
      (node (ref "U$3") (pin "D") (pinfunction "D_D") (pintype "bidirectional"))
    )
    (net (code "39") (name "Net-(C14-Pad2)") (class "Default")
      (node (ref "C14") (pin "2") (pinfunction "2_2") (pintype "passive"))
      (node (ref "J2") (pin "GND") (pinfunction "GND_GND") (pintype "power_in"))
      (node (ref "J2") (pin "SHLD1") (pinfunction "SHIELD_SHLD1") (pintype "bidirectional"))
      (node (ref "J2") (pin "SHLD2") (pinfunction "SHIELD_SHLD2") (pintype "bidirectional"))
      (node (ref "U$4") (pin "D") (pinfunction "D_D") (pintype "bidirectional"))
      (node (ref "U$5") (pin "D") (pinfunction "D_D") (pintype "bidirectional"))
    )
    (net (code "40") (name "Net-(C17-Pad2)") (class "Default")
      (node (ref "C17") (pin "2") (pinfunction "2_2") (pintype "passive"))
      (node (ref "J3") (pin "GND") (pinfunction "GND_GND") (pintype "power_in"))
      (node (ref "J3") (pin "SHLD1") (pinfunction "SHIELD_SHLD1") (pintype "bidirectional"))
      (node (ref "J3") (pin "SHLD2") (pinfunction "SHIELD_SHLD2") (pintype "bidirectional"))
      (node (ref "U$14") (pin "D") (pinfunction "D_D") (pintype "bidirectional"))
      (node (ref "U$15") (pin "D") (pinfunction "D_D") (pintype "bidirectional"))
    )
    (net (code "41") (name "Net-(C18-Pad2)") (class "Default")
      (node (ref "C18") (pin "2") (pinfunction "2_2") (pintype "passive"))
      (node (ref "J4") (pin "GND") (pinfunction "GND_GND") (pintype "power_in"))
      (node (ref "J4") (pin "SHLD1") (pinfunction "SHIELD_SHLD1") (pintype "bidirectional"))
      (node (ref "J4") (pin "SHLD2") (pinfunction "SHIELD_SHLD2") (pintype "bidirectional"))
      (node (ref "U$16") (pin "D") (pinfunction "D_D") (pintype "bidirectional"))
      (node (ref "U$17") (pin "D") (pinfunction "D_D") (pintype "bidirectional"))
    )
    (net (code "42") (name "Net-(C26-Pad1)") (class "Default")
      (node (ref "C26") (pin "1") (pinfunction "1_1") (pintype "passive"))
      (node (ref "R16") (pin "1") (pinfunction "1_1") (pintype "passive"))
      (node (ref "Y2") (pin "2") (pinfunction "2_2") (pintype "bidirectional"))
    )
    (net (code "43") (name "Net-(IC1-A0)") (class "Default")
      (node (ref "IC1") (pin "2") (pinfunction "A0_2") (pintype "bidirectional"))
      (node (ref "R8") (pin "1") (pinfunction "1_1") (pintype "passive"))
    )
    (net (code "44") (name "Net-(IC1-A1)") (class "Default")
      (node (ref "IC1") (pin "1") (pinfunction "A1_1") (pintype "bidirectional"))
      (node (ref "R7") (pin "1") (pinfunction "1_1") (pintype "passive"))
    )
    (net (code "45") (name "Net-(IC1-IN-)") (class "Default")
      (node (ref "C13") (pin "1") (pinfunction "1_1") (pintype "passive"))
      (node (ref "IC1") (pin "7") (pinfunction "IN-_7") (pintype "bidirectional"))
      (node (ref "J1") (pin "VBUS") (pinfunction "VBUS_VBUS") (pintype "power_in"))
      (node (ref "R9") (pin "1") (pinfunction "1_1") (pintype "passive"))
    )
    (net (code "46") (name "Net-(IC2-A1)") (class "Default")
      (node (ref "IC2") (pin "1") (pinfunction "A1_1") (pintype "bidirectional"))
      (node (ref "R12") (pin "1") (pinfunction "1_1") (pintype "passive"))
    )
    (net (code "47") (name "Net-(IC2-IN-)") (class "Default")
      (node (ref "C14") (pin "1") (pinfunction "1_1") (pintype "passive"))
      (node (ref "IC2") (pin "7") (pinfunction "IN-_7") (pintype "bidirectional"))
      (node (ref "J2") (pin "VBUS") (pinfunction "VBUS_VBUS") (pintype "power_in"))
      (node (ref "R10") (pin "1") (pinfunction "1_1") (pintype "passive"))
    )
    (net (code "48") (name "Net-(IC3-A0)") (class "Default")
      (node (ref "IC3") (pin "2") (pinfunction "A0_2") (pintype "bidirectional"))
      (node (ref "R30") (pin "1") (pinfunction "1_1") (pintype "passive"))
    )
    (net (code "49") (name "Net-(IC3-IN-)") (class "Default")
      (node (ref "C17") (pin "1") (pinfunction "1_1") (pintype "passive"))
      (node (ref "IC3") (pin "7") (pinfunction "IN-_7") (pintype "bidirectional"))
      (node (ref "J3") (pin "VBUS") (pinfunction "VBUS_VBUS") (pintype "power_in"))
      (node (ref "R11") (pin "1") (pinfunction "1_1") (pintype "passive"))
    )
    (net (code "50") (name "Net-(IC4-IN-)") (class "Default")
      (node (ref "C18") (pin "1") (pinfunction "1_1") (pintype "passive"))
      (node (ref "IC4") (pin "7") (pinfunction "IN-_7") (pintype "bidirectional"))
      (node (ref "J4") (pin "VBUS") (pinfunction "VBUS_VBUS") (pintype "power_in"))
      (node (ref "R14") (pin "1") (pinfunction "1_1") (pintype "passive"))
    )
    (net (code "51") (name "Net-(IC5-XTAL1)") (class "Default")
      (node (ref "C25") (pin "1") (pinfunction "1_1") (pintype "passive"))
      (node (ref "IC5") (pin "30") (pinfunction "XTAL1_30") (pintype "bidirectional"))
      (node (ref "Y2") (pin "1") (pinfunction "1_1") (pintype "bidirectional"))
    )
    (net (code "52") (name "Net-(IC5-XTAL2)") (class "Default")
      (node (ref "IC5") (pin "29") (pinfunction "XTAL2_29") (pintype "bidirectional"))
      (node (ref "R16") (pin "2") (pinfunction "2_2") (pintype "passive"))
    )
    (net (code "53") (name "Net-(IC5-~{RESET})") (class "Default")
      (node (ref "C24") (pin "1") (pinfunction "1_1") (pintype "passive"))
      (node (ref "IC5") (pin "4") (pinfunction "~{RESET}_4") (pintype "bidirectional"))
      (node (ref "R15") (pin "2") (pinfunction "2_2") (pintype "passive"))
    )
    (net (code "54") (name "Net-(NEOPIXEL1-DIN)") (class "Default")
      (node (ref "NEOPIXEL1") (pin "4") (pinfunction "DIN_4") (pintype "bidirectional"))
      (node (ref "R6") (pin "1") (pinfunction "1_1") (pintype "passive"))
    )
    (net (code "55") (name "Net-(NEOPIXEL1-DOUT)") (class "Default")
      (node (ref "NEOPIXEL1") (pin "2") (pinfunction "DOUT_2") (pintype "bidirectional"))
      (node (ref "NEOPIXEL2") (pin "4") (pinfunction "DIN_4") (pintype "bidirectional"))
    )
    (net (code "56") (name "Net-(NEOPIXEL2-DOUT)") (class "Default")
      (node (ref "NEOPIXEL2") (pin "2") (pinfunction "DOUT_2") (pintype "bidirectional"))
      (node (ref "NEOPIXEL3") (pin "4") (pinfunction "DIN_4") (pintype "bidirectional"))
    )
    (net (code "57") (name "Net-(NEOPIXEL3-DOUT)") (class "Default")
      (node (ref "NEOPIXEL3") (pin "2") (pinfunction "DOUT_2") (pintype "bidirectional"))
      (node (ref "NEOPIXEL4") (pin "4") (pinfunction "DIN_4") (pintype "bidirectional"))
    )
    (net (code "58") (name "RST") (class "Default")
      (node (ref "IC12") (pin "6") (pinfunction "~{RESET}_6") (pintype "bidirectional"))
      (node (ref "IC7") (pin "RST") (pinfunction "RST_RST") (pintype "input"))
      (node (ref "RESET") (pin "1") (pinfunction "COM_1") (pintype "bidirectional"))
      (node (ref "RN2") (pin "1") (pinfunction "1_1") (pintype "passive"))
    )
    (net (code "59") (name "RX") (class "Default")
      (node (ref "IC7") (pin "RXD/IO3") (pinfunction "RXD/IO3_RXD/IO3") (pintype "bidirectional"))
      (node (ref "PROGRAMMING") (pin "2") (pinfunction "2_2") (pintype "passive"))
    )
    (net (code "60") (name "S1+") (class "Default")
      (node (ref "IC11") (pin "8") (pinfunction "A_8") (pintype "bidirectional"))
      (node (ref "R2") (pin "2") (pinfunction "2_2") (pintype "passive"))
      (node (ref "R3") (pin "2") (pinfunction "2_2") (pintype "passive"))
      (node (ref "U$6") (pin "4") (pinfunction "COM_4") (pintype "bidirectional"))
    )
    (net (code "61") (name "S1-") (class "Default")
      (node (ref "IC11") (pin "6") (pinfunction "B_6") (pintype "bidirectional"))
      (node (ref "R1") (pin "2") (pinfunction "2_2") (pintype "passive"))
      (node (ref "R4") (pin "2") (pinfunction "2_2") (pintype "passive"))
      (node (ref "U$7") (pin "4") (pinfunction "COM_4") (pintype "bidirectional"))
    )
    (net (code "62") (name "S2+") (class "Default")
      (node (ref "IC11") (pin "4") (pinfunction "D_4") (pintype "bidirectional"))
      (node (ref "R17") (pin "2") (pinfunction "2_2") (pintype "passive"))
      (node (ref "R18") (pin "2") (pinfunction "2_2") (pintype "passive"))
      (node (ref "U$8") (pin "4") (pinfunction "COM_4") (pintype "bidirectional"))
    )
    (net (code "63") (name "S2-") (class "Default")
      (node (ref "IC11") (pin "2") (pinfunction "C_2") (pintype "bidirectional"))
      (node (ref "R13") (pin "2") (pinfunction "2_2") (pintype "passive"))
      (node (ref "R19") (pin "2") (pinfunction "2_2") (pintype "passive"))
      (node (ref "U$9") (pin "4") (pinfunction "COM_4") (pintype "bidirectional"))
    )
    (net (code "64") (name "S3+") (class "Default")
      (node (ref "IC10") (pin "8") (pinfunction "A_8") (pintype "bidirectional"))
      (node (ref "R23") (pin "2") (pinfunction "2_2") (pintype "passive"))
      (node (ref "R24") (pin "2") (pinfunction "2_2") (pintype "passive"))
      (node (ref "U$10") (pin "4") (pinfunction "COM_4") (pintype "bidirectional"))
    )
    (net (code "65") (name "S3-") (class "Default")
      (node (ref "IC10") (pin "6") (pinfunction "B_6") (pintype "bidirectional"))
      (node (ref "R20") (pin "2") (pinfunction "2_2") (pintype "passive"))
      (node (ref "R25") (pin "2") (pinfunction "2_2") (pintype "passive"))
      (node (ref "U$11") (pin "4") (pinfunction "COM_4") (pintype "bidirectional"))
    )
    (net (code "66") (name "S4+") (class "Default")
      (node (ref "IC10") (pin "4") (pinfunction "D_4") (pintype "bidirectional"))
      (node (ref "R27") (pin "2") (pinfunction "2_2") (pintype "passive"))
      (node (ref "R28") (pin "2") (pinfunction "2_2") (pintype "passive"))
      (node (ref "U$12") (pin "4") (pinfunction "COM_4") (pintype "bidirectional"))
    )
    (net (code "67") (name "S4-") (class "Default")
      (node (ref "IC10") (pin "2") (pinfunction "C_2") (pintype "bidirectional"))
      (node (ref "R26") (pin "2") (pinfunction "2_2") (pintype "passive"))
      (node (ref "R29") (pin "2") (pinfunction "2_2") (pintype "passive"))
      (node (ref "U$13") (pin "4") (pinfunction "COM_4") (pintype "bidirectional"))
    )
    (net (code "68") (name "SCL") (class "Default")
      (node (ref "I2C") (pin "3") (pinfunction "3_3") (pintype "passive"))
      (node (ref "IC1") (pin "4") (pinfunction "SCL_4") (pintype "bidirectional"))
      (node (ref "IC12") (pin "1") (pinfunction "SCL_1") (pintype "bidirectional"))
      (node (ref "IC2") (pin "4") (pinfunction "SCL_4") (pintype "bidirectional"))
      (node (ref "IC3") (pin "4") (pinfunction "SCL_4") (pintype "bidirectional"))
      (node (ref "IC4") (pin "4") (pinfunction "SCL_4") (pintype "bidirectional"))
      (node (ref "IC7") (pin "IO5") (pinfunction "IO5_IO5") (pintype "bidirectional"))
      (node (ref "R21") (pin "1") (pinfunction "1_1") (pintype "passive"))
    )
    (net (code "69") (name "SDA") (class "Default")
      (node (ref "I2C") (pin "4") (pinfunction "4_4") (pintype "passive"))
      (node (ref "IC1") (pin "3") (pinfunction "SDA_3") (pintype "bidirectional"))
      (node (ref "IC12") (pin "2") (pinfunction "SDA_2") (pintype "bidirectional"))
      (node (ref "IC2") (pin "3") (pinfunction "SDA_3") (pintype "bidirectional"))
      (node (ref "IC3") (pin "3") (pinfunction "SDA_3") (pintype "bidirectional"))
      (node (ref "IC4") (pin "3") (pinfunction "SDA_3") (pintype "bidirectional"))
      (node (ref "IC7") (pin "IO4") (pinfunction "IO4_IO4") (pintype "bidirectional"))
      (node (ref "R22") (pin "1") (pinfunction "1_1") (pintype "passive"))
    )
    (net (code "70") (name "TX") (class "Default")
      (node (ref "IC7") (pin "TXD/IO1") (pinfunction "TXD/IO1_TXD/IO1") (pintype "bidirectional"))
      (node (ref "PROGRAMMING") (pin "1") (pinfunction "1_1") (pintype "passive"))
    )
    (net (code "71") (name "VCC") (class "Default")
      (node (ref "C15") (pin "2") (pinfunction "2_2") (pintype "passive"))
      (node (ref "C16") (pin "2") (pinfunction "2_2") (pintype "passive"))
      (node (ref "C19") (pin "1") (pinfunction "1_1") (pintype "passive"))
      (node (ref "C2") (pin "1") (pinfunction "1_1") (pintype "passive"))
      (node (ref "C27") (pin "1") (pinfunction "1_1") (pintype "passive"))
      (node (ref "C3") (pin "1") (pinfunction "1_1") (pintype "passive"))
      (node (ref "C36") (pin "1") (pinfunction "+_1") (pintype "bidirectional"))
      (node (ref "C4") (pin "1") (pinfunction "1_1") (pintype "passive"))
      (node (ref "I2C") (pin "2") (pinfunction "2_2") (pintype "passive"))
      (node (ref "IC1") (pin "5") (pinfunction "VS_5") (pintype "bidirectional"))
      (node (ref "IC12") (pin "18") (pinfunction "VCC_18") (pintype "bidirectional"))
      (node (ref "IC2") (pin "2") (pinfunction "A0_2") (pintype "bidirectional"))
      (node (ref "IC2") (pin "5") (pinfunction "VS_5") (pintype "bidirectional"))
      (node (ref "IC3") (pin "1") (pinfunction "A1_1") (pintype "bidirectional"))
      (node (ref "IC3") (pin "5") (pinfunction "VS_5") (pintype "bidirectional"))
      (node (ref "IC4") (pin "1") (pinfunction "A1_1") (pintype "bidirectional"))
      (node (ref "IC4") (pin "2") (pinfunction "A0_2") (pintype "bidirectional"))
      (node (ref "IC4") (pin "5") (pinfunction "VS_5") (pintype "bidirectional"))
      (node (ref "IC5") (pin "10") (pinfunction "~{OVRCUR1}_10") (pintype "bidirectional"))
      (node (ref "IC5") (pin "14") (pinfunction "~{OVRCUR2}_14") (pintype "bidirectional"))
      (node (ref "IC5") (pin "18") (pinfunction "~{OVRCUR3}_18") (pintype "bidirectional"))
      (node (ref "IC5") (pin "22") (pinfunction "~{OVRCUR4}_22") (pintype "bidirectional"))
      (node (ref "IC5") (pin "25") (pinfunction "VCC_2_25") (pintype "bidirectional"))
      (node (ref "IC5") (pin "26") (pinfunction "~{EXTMEM}_26") (pintype "bidirectional"))
      (node (ref "IC5") (pin "3") (pinfunction "VCC_1_3") (pintype "bidirectional"))
      (node (ref "IC7") (pin "EN") (pinfunction "EN_EN") (pintype "bidirectional"))
      (node (ref "IC7") (pin "VCC") (pinfunction "VCC_VCC") (pintype "power_in"))
      (node (ref "IC8") (pin "2") (pinfunction "VOUT_2") (pintype "bidirectional"))
      (node (ref "IC8") (pin "4") (pinfunction "OUTPUT_4") (pintype "bidirectional"))
      (node (ref "NEOPIXEL1") (pin "1") (pinfunction "VDD_1") (pintype "bidirectional"))
      (node (ref "NEOPIXEL2") (pin "1") (pinfunction "VDD_1") (pintype "bidirectional"))
      (node (ref "NEOPIXEL3") (pin "1") (pinfunction "VDD_1") (pintype "bidirectional"))
      (node (ref "NEOPIXEL4") (pin "1") (pinfunction "VDD_1") (pintype "bidirectional"))
      (node (ref "R15") (pin "1") (pinfunction "1_1") (pintype "passive"))
      (node (ref "R21") (pin "2") (pinfunction "2_2") (pintype "passive"))
      (node (ref "R22") (pin "2") (pinfunction "2_2") (pintype "passive"))
      (node (ref "R5") (pin "1") (pinfunction "1_1") (pintype "passive"))
      (node (ref "RN2") (pin "6") (pinfunction "2_6") (pintype "passive"))
      (node (ref "RN2") (pin "7") (pinfunction "2_7") (pintype "passive"))
      (node (ref "RN2") (pin "8") (pinfunction "2_8") (pintype "passive"))
      (node (ref "RN3") (pin "5") (pinfunction "2_5") (pintype "passive"))
      (node (ref "RN3") (pin "6") (pinfunction "2_6") (pintype "passive"))
      (node (ref "RN3") (pin "7") (pinfunction "2_7") (pintype "passive"))
      (node (ref "RN3") (pin "8") (pinfunction "2_8") (pintype "passive"))
      (node (ref "U$10") (pin "5") (pinfunction "V+_5") (pintype "bidirectional"))
      (node (ref "U$11") (pin "5") (pinfunction "V+_5") (pintype "bidirectional"))
      (node (ref "U$12") (pin "5") (pinfunction "V+_5") (pintype "bidirectional"))
      (node (ref "U$13") (pin "5") (pinfunction "V+_5") (pintype "bidirectional"))
      (node (ref "U$6") (pin "5") (pinfunction "V+_5") (pintype "bidirectional"))
      (node (ref "U$7") (pin "5") (pinfunction "V+_5") (pintype "bidirectional"))
      (node (ref "U$8") (pin "5") (pinfunction "V+_5") (pintype "bidirectional"))
      (node (ref "U$9") (pin "5") (pinfunction "V+_5") (pintype "bidirectional"))
    )
    (net (code "72") (name "VIN") (class "Default")
      (node (ref "C21") (pin "1") (pinfunction "1_1") (pintype "passive"))
      (node (ref "C22") (pin "1") (pinfunction "1_1") (pintype "passive"))
      (node (ref "IC1") (pin "8") (pinfunction "IN+_8") (pintype "bidirectional"))
      (node (ref "IC2") (pin "8") (pinfunction "IN+_8") (pintype "bidirectional"))
      (node (ref "IC3") (pin "8") (pinfunction "IN+_8") (pintype "bidirectional"))
      (node (ref "IC4") (pin "8") (pinfunction "IN+_8") (pintype "bidirectional"))
      (node (ref "IC8") (pin "3") (pinfunction "VIN_3") (pintype "bidirectional"))
      (node (ref "POWER") (pin "1") (pinfunction "1_1") (pintype "passive"))
      (node (ref "R10") (pin "2") (pinfunction "2_2") (pintype "passive"))
      (node (ref "R11") (pin "2") (pinfunction "2_2") (pintype "passive"))
      (node (ref "R14") (pin "2") (pinfunction "2_2") (pintype "passive"))
      (node (ref "R9") (pin "2") (pinfunction "2_2") (pintype "passive"))
    )
    (net (code "73") (name "unconnected-(IC5-EECLK-Pad5)") (class "Default")
      (node (ref "IC5") (pin "5") (pinfunction "EECLK_5") (pintype "bidirectional"))
    )
    (net (code "74") (name "unconnected-(IC5-EP-Pad33)") (class "Default")
      (node (ref "IC5") (pin "33") (pinfunction "EP_33") (pintype "bidirectional"))
    )
    (net (code "75") (name "unconnected-(IC5-TSTPLL{slash}48MCLK-Pad27)") (class "Default")
      (node (ref "IC5") (pin "27") (pinfunction "TSTPLL/48MCLK_27") (pintype "bidirectional"))
    )
    (net (code "76") (name "unconnected-(IC5-~{PWRON1}-Pad9)") (class "Default")
      (node (ref "IC5") (pin "9") (pinfunction "~{PWRON1}_9") (pintype "bidirectional"))
    )
    (net (code "77") (name "unconnected-(IC5-~{PWRON2}-Pad13)") (class "Default")
      (node (ref "IC5") (pin "13") (pinfunction "~{PWRON2}_13") (pintype "bidirectional"))
    )
    (net (code "78") (name "unconnected-(IC5-~{PWRON3}-Pad17)") (class "Default")
      (node (ref "IC5") (pin "17") (pinfunction "~{PWRON3}_17") (pintype "bidirectional"))
    )
    (net (code "79") (name "unconnected-(IC5-~{PWRON4}-Pad21)") (class "Default")
      (node (ref "IC5") (pin "21") (pinfunction "~{PWRON4}_21") (pintype "bidirectional"))
    )
    (net (code "80") (name "unconnected-(IC7-PadADC)") (class "Default")
      (node (ref "IC7") (pin "ADC") (pinfunction "ADC_ADC") (pintype "bidirectional"))
    )
    (net (code "81") (name "unconnected-(IC7-PadCS0)") (class "Default")
      (node (ref "IC7") (pin "CS0") (pinfunction "CS0_CS0") (pintype "bidirectional"))
    )
    (net (code "82") (name "unconnected-(IC7-PadIO9)") (class "Default")
      (node (ref "IC7") (pin "IO9") (pinfunction "IO9_IO9") (pintype "bidirectional"))
    )
    (net (code "83") (name "unconnected-(IC7-PadIO10)") (class "Default")
      (node (ref "IC7") (pin "IO10") (pinfunction "IO10_IO10") (pintype "bidirectional"))
    )
    (net (code "84") (name "unconnected-(IC7-PadIO16)") (class "Default")
      (node (ref "IC7") (pin "IO16") (pinfunction "IO16_IO16") (pintype "bidirectional"))
    )
    (net (code "85") (name "unconnected-(IC7-PadMISO)") (class "Default")
      (node (ref "IC7") (pin "MISO") (pinfunction "MISO_MISO") (pintype "bidirectional"))
    )
    (net (code "86") (name "unconnected-(IC7-PadMOSI)") (class "Default")
      (node (ref "IC7") (pin "MOSI") (pinfunction "MOSI_MOSI") (pintype "bidirectional"))
    )
    (net (code "87") (name "unconnected-(IC7-PadSCLK)") (class "Default")
      (node (ref "IC7") (pin "SCLK") (pinfunction "SCLK_SCLK") (pintype "bidirectional"))
    )
    (net (code "88") (name "unconnected-(IC9-A-Pad8)") (class "Default")
      (node (ref "IC9") (pin "8") (pinfunction "A_8") (pintype "bidirectional"))
    )
    (net (code "89") (name "unconnected-(IC9-B-Pad6)") (class "Default")
      (node (ref "IC9") (pin "6") (pinfunction "B_6") (pintype "bidirectional"))
    )
    (net (code "90") (name "unconnected-(IC9-GND_3-Pad5)") (class "Default")
      (node (ref "IC9") (pin "5") (pinfunction "GND_3_5") (pintype "bidirectional"))
    )
    (net (code "91") (name "unconnected-(IC9-GND_4-Pad7)") (class "Default")
      (node (ref "IC9") (pin "7") (pinfunction "GND_4_7") (pintype "bidirectional"))
    )
    (net (code "92") (name "unconnected-(IC12-NC-Pad7)") (class "Default")
      (node (ref "IC12") (pin "7") (pinfunction "NC_7") (pintype "no_connect"))
    )
    (net (code "93") (name "unconnected-(NEOPIXEL4-DOUT-Pad2)") (class "Default")
      (node (ref "NEOPIXEL4") (pin "2") (pinfunction "DOUT_2") (pintype "bidirectional"))
    )
    (net (code "94") (name "unconnected-(RN1D-2-Pad5)") (class "Default")
      (node (ref "RN1") (pin "5") (pinfunction "2_5") (pintype "passive"))
    )
    (net (code "95") (name "unconnected-(RN3-Pad1)") (class "Default")
      (node (ref "RN3") (pin "1") (pinfunction "1_1") (pintype "passive"))
    )
    (net (code "96") (name "unconnected-(U$6-NC-Pad3)") (class "Default")
      (node (ref "U$6") (pin "3") (pinfunction "NC_3") (pintype "no_connect"))
    )
    (net (code "97") (name "unconnected-(U$7-NC-Pad3)") (class "Default")
      (node (ref "U$7") (pin "3") (pinfunction "NC_3") (pintype "no_connect"))
    )
    (net (code "98") (name "unconnected-(U$8-NC-Pad3)") (class "Default")
      (node (ref "U$8") (pin "3") (pinfunction "NC_3") (pintype "no_connect"))
    )
    (net (code "99") (name "unconnected-(U$9-NC-Pad3)") (class "Default")
      (node (ref "U$9") (pin "3") (pinfunction "NC_3") (pintype "no_connect"))
    )
    (net (code "100") (name "unconnected-(U$10-NC-Pad3)") (class "Default")
      (node (ref "U$10") (pin "3") (pinfunction "NC_3") (pintype "no_connect"))
    )
    (net (code "101") (name "unconnected-(U$11-NC-Pad3)") (class "Default")
      (node (ref "U$11") (pin "3") (pinfunction "NC_3") (pintype "no_connect"))
    )
    (net (code "102") (name "unconnected-(U$12-NC-Pad3)") (class "Default")
      (node (ref "U$12") (pin "3") (pinfunction "NC_3") (pintype "no_connect"))
    )
    (net (code "103") (name "unconnected-(U$13-NC-Pad3)") (class "Default")
      (node (ref "U$13") (pin "3") (pinfunction "NC_3") (pintype "no_connect"))
    )
    (net (code "104") (name "unconnected-(USBIN-PadVBUS)") (class "Default")
      (node (ref "USBIN") (pin "VBUS") (pinfunction "VBUS_VBUS") (pintype "bidirectional"))
    )
  )
)
